# PAGE06.net
KiCad netlist of a schematic drawn in Altium Designer
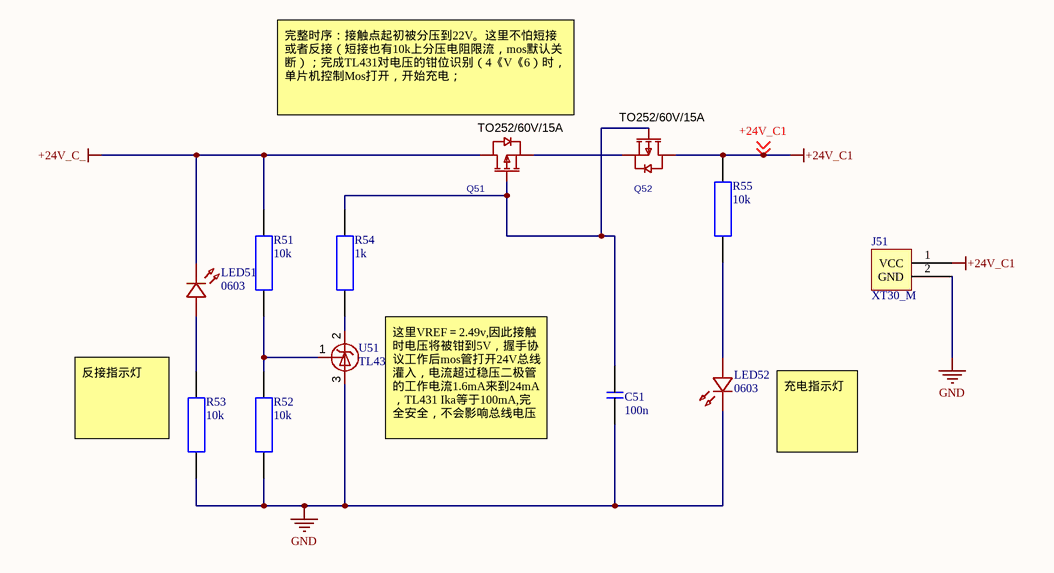
[diagram p0: PAGE06_握手协议飞机端.SchDoc]

(export (version "E")
  (design (tool "Eeschema 10.0.6"))
  (components
    (comp (ref "C51") (value "100n") (footprint "0603_ding_C") (libsource (lib "IP6826") (part "C")))
    (comp (ref "J51")
      (value "XT30_M")
      (footprint "RobotLab_Common_Used:XT30（立式）")
      (libsource (lib "RobotLab_Common_Used") (part "XT30_M"))
    )
    (comp (ref "LED51")
      (value "0603")
      (footprint "LED0603-RD_GREEN")
      (libsource (lib "IP6826") (part "LED0603"))
    )
    (comp (ref "LED52")
      (value "0603")
      (footprint "LED0603-RD_GREEN")
      (libsource (lib "IP6826") (part "LED0603"))
    )
    (comp (ref "Q51")
      (value "TO252/60V/15A")
      (footprint "TO-252-2_L6.6-W6.1-P4.57-LS9.9-BR-CW")
      (description "数量:1个P沟道;漏源电压(Vdss):40V;连续漏极电流(Id):40A;导通电阻(RDS(on)):15mΩ@10V;耗散功率(Pd):62.5W;阈值电压(Vgs(th)):3V;")
      (fields (field (name "MANUFACTURER") "AOS") (field (name "MANUFACTURERPART") "AOD4185"))
      (libsource (lib "AOD4185_C400894") (part "aod4185_c400894"))
    )
    (comp (ref "Q52")
      (value "TO252/60V/15A")
      (footprint "TO-252-2_L6.6-W6.1-P4.57-LS9.9-BR-CW")
      (description "数量:1个P沟道;漏源电压(Vdss):40V;连续漏极电流(Id):40A;导通电阻(RDS(on)):15mΩ@10V;耗散功率(Pd):62.5W;阈值电压(Vgs(th)):3V;")
      (fields (field (name "MANUFACTURER") "AOS") (field (name "MANUFACTURERPART") "AOD4185"))
      (libsource (lib "AOD4185_C400894") (part "aod4185_c400894"))
    )
    (comp (ref "R51") (value "10k") (footprint "0603_ding_R") (libsource (lib "IP6826") (part "RES")))
    (comp (ref "R52") (value "10k") (footprint "0603_ding_R") (libsource (lib "IP6826") (part "RES")))
    (comp (ref "R53") (value "10k") (footprint "0603_ding_R") (libsource (lib "IP6826") (part "RES")))
    (comp (ref "R54") (value "1k") (footprint "0603_ding_R") (libsource (lib "IP6826") (part "RES")))
    (comp (ref "R55") (value "10k") (footprint "0603_ding_R") (libsource (lib "IP6826") (part "RES")))
    (comp (ref "U51")
      (value "TL431")
      (footprint "SOT-23-3_L3.0-W1.6-P1.90-LS2.8-BR")
      (libsource (lib "IP6826") (part "TL431"))
    )
  )
  (nets
    (net (code "1") (name "+24V_C1") (class "Default")
      (node (ref "J51") (pin "1") (pinfunction "VCC_1") (pintype "passive"))
      (node (ref "Q52") (pin "2") (pinfunction "D_2") (pintype "passive"))
      (node (ref "R55") (pin "1") (pinfunction "1_1") (pintype "passive"))
    )
    (net (code "2") (name "+24V_C_") (class "Default")
      (node (ref "LED51") (pin "1") (pinfunction "C_1") (pintype "passive"))
      (node (ref "Q51") (pin "2") (pinfunction "D_2") (pintype "passive"))
      (node (ref "R51") (pin "2") (pinfunction "2_2") (pintype "passive"))
    )
    (net (code "3") (name "GND") (class "Default")
      (node (ref "C51") (pin "1") (pinfunction "1_1") (pintype "passive"))
      (node (ref "J51") (pin "2") (pinfunction "GND_2") (pintype "passive"))
      (node (ref "LED52") (pin "1") (pinfunction "C_1") (pintype "passive"))
      (node (ref "R52") (pin "1") (pinfunction "1_1") (pintype "passive"))
      (node (ref "R53") (pin "1") (pinfunction "1_1") (pintype "passive"))
      (node (ref "U51") (pin "3") (pinfunction "A_3") (pintype "passive"))
    )
    (net (code "4") (name "Net-(LED51-A)") (class "Default")
      (node (ref "LED51") (pin "2") (pinfunction "A_2") (pintype "passive"))
      (node (ref "R53") (pin "2") (pinfunction "2_2") (pintype "passive"))
    )
    (net (code "5") (name "Net-(LED52-A)") (class "Default")
      (node (ref "LED52") (pin "2") (pinfunction "A_2") (pintype "passive"))
      (node (ref "R55") (pin "2") (pinfunction "2_2") (pintype "passive"))
    )
    (net (code "6") (name "Net-(Q51-G)") (class "Default")
      (node (ref "C51") (pin "2") (pinfunction "2_2") (pintype "passive"))
      (node (ref "Q51") (pin "1") (pinfunction "G_1") (pintype "passive"))
      (node (ref "Q52") (pin "1") (pinfunction "G_1") (pintype "passive"))
      (node (ref "R54") (pin "2") (pinfunction "2_2") (pintype "passive"))
    )
    (net (code "7") (name "Net-(Q51-S)") (class "Default")
      (node (ref "Q51") (pin "3") (pinfunction "S_3") (pintype "passive"))
      (node (ref "Q52") (pin "3") (pinfunction "S_3") (pintype "passive"))
    )
    (net (code "8") (name "Net-(U51-K)") (class "Default")
      (node (ref "R54") (pin "1") (pinfunction "1_1") (pintype "passive"))
      (node (ref "U51") (pin "2") (pinfunction "K_2") (pintype "passive"))
    )
    (net (code "9") (name "Net-(U51-R)") (class "Default")
      (node (ref "R51") (pin "1") (pinfunction "1_1") (pintype "passive"))
      (node (ref "R52") (pin "2") (pinfunction "2_2") (pintype "passive"))
      (node (ref "U51") (pin "1") (pinfunction "R_1") (pintype "passive"))
    )
  )
)
